# External_Camera_HAT_Regulators.net
KiCad netlist of a schematic drawn in Altium Designer
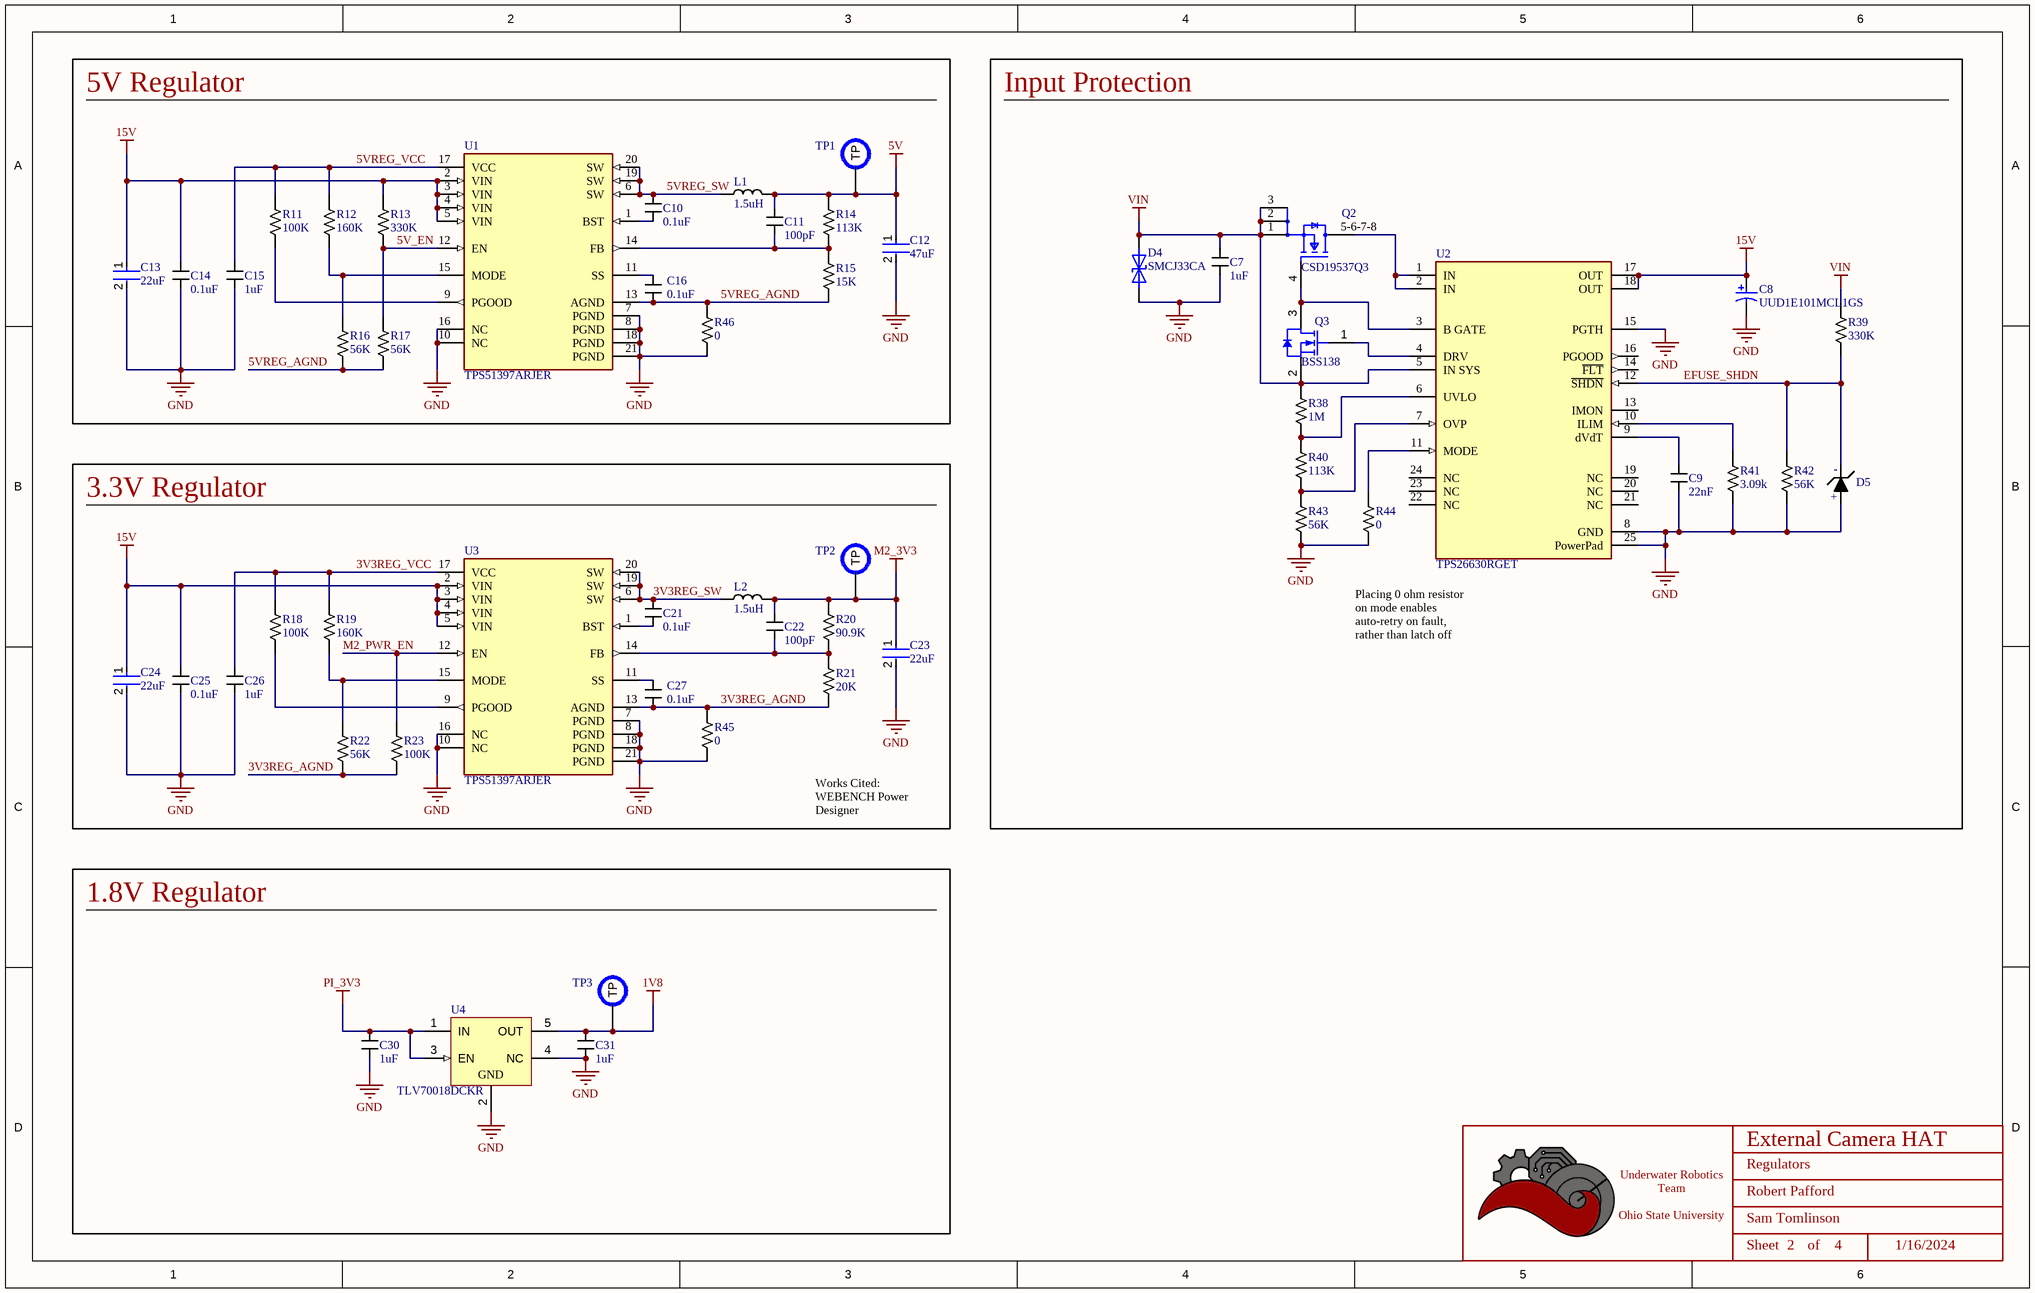
[diagram p0: External_Camera_HAT_Regulators.SchDoc]

(export (version "E")
  (design (tool "Eeschema 10.0.6"))
  (components
    (comp (ref "C7")
      (value "1uF")
      (footprint "CAPACITOR_0603")
      (description "Cap 1uF 25V +/-10%\r\nCeramic 0603")
      (fields
        (field (name "TOLERANCE") "+/- 10%")
        (field (name "VOLTAGE") "16V")
        (field (name "MADE BY") "Flip B")
      )
      (libsource (lib "Capacitors") (part "CAPACITOR_1uF_0603_25V"))
    )
    (comp (ref "C8")
      (value "UUD1E101MCL1GS")
      (footprint "NIC-CAPA2-6.3X7.7_V")
      (fields (field (name "MANUFACTURER") "Nichicon"))
      (libsource (lib "Altium Content Vault") (part "NIC-CAP-P-2"))
    )
    (comp (ref "C9")
      (value "22nF")
      (footprint "CAPACITOR_0402")
      (description "Cap 22nF 25V +/-10%\r\nCeramic 0402")
      (fields
        (field (name "TOLERANCE") "+/- 10%")
        (field (name "VOLTAGE") "25V")
        (field (name "MADE BY") "Robert Pafford")
      )
      (libsource (lib "Capacitors") (part "CAPACITOR_0.022uF_0402"))
    )
    (comp (ref "C10")
      (value "0.1uF")
      (footprint "CAPACITOR_0402")
      (description "Cap 100nF 25V +/-10%\r\nCeramic 0402")
      (fields
        (field (name "TOLERANCE") "+/- 10%")
        (field (name "VOLTAGE") "25V")
        (field (name "MADE BY") "Robert Pafford")
      )
      (libsource (lib "Capacitors") (part "CAPACITOR_0.1uF_0402"))
    )
    (comp (ref "C11")
      (value "100pF")
      (footprint "CAPACITOR_0402")
      (description "Cap 100pF 25V +/-10%\r\nCeramic 0402")
      (fields
        (field (name "TOLERANCE") "+/- 10%")
        (field (name "VOLTAGE") "25V")
        (field (name "MADE BY") "Robert Pafford")
      )
      (libsource (lib "Capacitors") (part "CAPACITOR_0.0001uF_0402"))
    )
    (comp (ref "C12")
      (value "GRM31CR61A476KE15L")
      (footprint "FP-GRM31C-0_2-e0_3_0_8-MFG")
      (description "Chip Multilayer Ceramic Capacitors for General Purpose, 1206, 47uF, X5R, 15%, 10%, 10V")
      (fields
        (field (name "TOLERANCE") "10%")
        (field (name "VOLTAGE") "10V")
        (field (name "CAPACITANCE") "47uF")
      )
      (libsource (lib "Altium Content Vault") (part "02cd4be3c70576c341d710602a673aa"))
    )
    (comp (ref "C13")
      (value "C2012X5R1V226M125AC")
      (footprint "FP-C2012-125-0_2-MFG")
      (description "Multilayer Ceramic Capacitors 22μF ±20% 35V X5R SMD 0805")
      (fields (field (name "TOLERANCE") "20%") (field (name "CAPACITANCE") "22uF"))
      (libsource (lib "Altium Content Vault") (part "b4654b650e69147ec39a6b967a45e02"))
    )
    (comp (ref "C14")
      (value "0.1uF")
      (footprint "CAPACITOR_0402")
      (description "Cap 100nF 25V +/-10%\r\nCeramic 0402")
      (fields
        (field (name "TOLERANCE") "+/- 10%")
        (field (name "VOLTAGE") "25V")
        (field (name "MADE BY") "Robert Pafford")
      )
      (libsource (lib "Capacitors") (part "CAPACITOR_0.1uF_0402"))
    )
    (comp (ref "C15")
      (value "1uF")
      (footprint "CAPACITOR_0402")
      (description "Cap 1uF 16V +/-10%\r\nCeramic 0402")
      (fields
        (field (name "TOLERANCE") "+/- 10%")
        (field (name "VOLTAGE") "16V")
        (field (name "MADE BY") "Robert Pafford")
      )
      (libsource (lib "Capacitors") (part "CAPACITOR_1uF_0402"))
    )
    (comp (ref "C16")
      (value "0.1uF")
      (footprint "CAPACITOR_0402")
      (description "Cap 100nF 25V +/-10%\r\nCeramic 0402")
      (fields
        (field (name "TOLERANCE") "+/- 10%")
        (field (name "VOLTAGE") "25V")
        (field (name "MADE BY") "Robert Pafford")
      )
      (libsource (lib "Capacitors") (part "CAPACITOR_0.1uF_0402"))
    )
    (comp (ref "C21")
      (value "0.1uF")
      (footprint "CAPACITOR_0402")
      (description "Cap 100nF 25V +/-10%\r\nCeramic 0402")
      (fields
        (field (name "TOLERANCE") "+/- 10%")
        (field (name "VOLTAGE") "25V")
        (field (name "MADE BY") "Robert Pafford")
      )
      (libsource (lib "Capacitors") (part "CAPACITOR_0.1uF_0402"))
    )
    (comp (ref "C22")
      (value "100pF")
      (footprint "CAPACITOR_0402")
      (description "Cap 100pF 25V +/-10%\r\nCeramic 0402")
      (fields
        (field (name "TOLERANCE") "+/- 10%")
        (field (name "VOLTAGE") "25V")
        (field (name "MADE BY") "Robert Pafford")
      )
      (libsource (lib "Capacitors") (part "CAPACITOR_0.0001uF_0402"))
    )
    (comp (ref "C23")
      (value "C2012X5R1V226M125AC")
      (footprint "FP-C2012-125-0_2-MFG")
      (description "Multilayer Ceramic Capacitors 22μF ±20% 35V X5R SMD 0805")
      (fields (field (name "TOLERANCE") "20%") (field (name "CAPACITANCE") "22uF"))
      (libsource (lib "Altium Content Vault") (part "b4654b650e69147ec39a6b967a45e02"))
    )
    (comp (ref "C24")
      (value "C2012X5R1V226M125AC")
      (footprint "FP-C2012-125-0_2-MFG")
      (description "Multilayer Ceramic Capacitors 22μF ±20% 35V X5R SMD 0805")
      (fields (field (name "TOLERANCE") "20%") (field (name "CAPACITANCE") "22uF"))
      (libsource (lib "Altium Content Vault") (part "b4654b650e69147ec39a6b967a45e02"))
    )
    (comp (ref "C25")
      (value "0.1uF")
      (footprint "CAPACITOR_0402")
      (description "Cap 100nF 25V +/-10%\r\nCeramic 0402")
      (fields
        (field (name "TOLERANCE") "+/- 10%")
        (field (name "VOLTAGE") "25V")
        (field (name "MADE BY") "Robert Pafford")
      )
      (libsource (lib "Capacitors") (part "CAPACITOR_0.1uF_0402"))
    )
    (comp (ref "C26")
      (value "1uF")
      (footprint "CAPACITOR_0402")
      (description "Cap 1uF 16V +/-10%\r\nCeramic 0402")
      (fields
        (field (name "TOLERANCE") "+/- 10%")
        (field (name "VOLTAGE") "16V")
        (field (name "MADE BY") "Robert Pafford")
      )
      (libsource (lib "Capacitors") (part "CAPACITOR_1uF_0402"))
    )
    (comp (ref "C27")
      (value "0.1uF")
      (footprint "CAPACITOR_0402")
      (description "Cap 100nF 25V +/-10%\r\nCeramic 0402")
      (fields
        (field (name "TOLERANCE") "+/- 10%")
        (field (name "VOLTAGE") "25V")
        (field (name "MADE BY") "Robert Pafford")
      )
      (libsource (lib "Capacitors") (part "CAPACITOR_0.1uF_0402"))
    )
    (comp (ref "C30")
      (value "1uF")
      (footprint "CAPACITOR_0402")
      (description "Cap 1uF 16V +/-10%\r\nCeramic 0402")
      (fields
        (field (name "TOLERANCE") "+/- 10%")
        (field (name "VOLTAGE") "16V")
        (field (name "MADE BY") "Robert Pafford")
      )
      (libsource (lib "Capacitors") (part "CAPACITOR_1uF_0402"))
    )
    (comp (ref "C31")
      (value "1uF")
      (footprint "CAPACITOR_0402")
      (description "Cap 1uF 16V +/-10%\r\nCeramic 0402")
      (fields
        (field (name "TOLERANCE") "+/- 10%")
        (field (name "VOLTAGE") "16V")
        (field (name "MADE BY") "Robert Pafford")
      )
      (libsource (lib "Capacitors") (part "CAPACITOR_1uF_0402"))
    )
    (comp (ref "D4")
      (value "SMCJ33CA")
      (footprint "DIOM7959X262N")
      (description "53.3V Clamp 28.1A Ipp Tvs Diode Surface Mount SMC (DO-214AB)")
      (fields (field (name "MF") "Bourns Inc."))
      (libsource (lib "Diodes") (part "SMCJ33CA"))
    )
    (comp (ref "D5")
      (value "Zener_Diode_3.3V_250mW_1")
      (footprint "SOD-123")
      (description "Zener Diode ¦ 3.3 V ¦ 250 mW ¦ SOT-23")
      (fields (field (name "POWER") "410mW") (field (name "MADE BY") "Nathan A"))
      (libsource (lib "Diodes") (part "Zener_Diode_3.3V_250mW_1"))
    )
    (comp (ref "L1")
      (value "1.5uH")
      (footprint "IHLP2525EZ")
      (description "Inductor Shielded 1.5uH 12A +/-20%")
      (fields
        (field (name "TOLERANCE") "+/- 20%")
        (field (name "Comment") "1.5uH Shielded")
        (field (name "MADE BY") "Robert Pafford")
      )
      (libsource (lib "Inductors") (part "INDUCTOR_1.5uH_IHLP2525EZ_1"))
    )
    (comp (ref "L2")
      (value "1.5uH")
      (footprint "IHLP2525EZ")
      (description "Inductor Shielded 1.5uH 12A +/-20%")
      (fields
        (field (name "TOLERANCE") "+/- 20%")
        (field (name "Comment") "1.5uH Shielded")
        (field (name "MADE BY") "Robert Pafford")
      )
      (libsource (lib "Inductors") (part "INDUCTOR_1.5uH_IHLP2525EZ_1"))
    )
    (comp (ref "Q2")
      (value "CSD19537Q3")
      (footprint "FP-DQG0008A-MFG")
      (description "MOSFET N-CH 100V 50A 8VSON")
      (libsource (lib "Altium Content Vault") (part "7382af88e928fdc71488234cfaaf11c"))
    )
    (comp (ref "Q3")
      (value "BSS138")
      (footprint "FAIR-SOT23-3_V")
      (fields (field (name "MANUFACTURER") "Fairchild") (field (name "POWER") "360mW"))
      (libsource (lib "Ohio State Capstone Team 20") (part "NEMOS-GSD-3"))
    )
    (comp (ref "R11")
      (value "100k Ohm 1% 1/16W")
      (footprint "RESISTOR_0402")
      (description "RES 100k OHM 1% 1/16W 0402")
      (fields
        (field (name "TOLERANCE") "+/- 1%")
        (field (name "VALUE  (OHMS)") "100K")
        (field (name "MADE BY") "Robert Pafford")
      )
      (libsource (lib "Resistors") (part "RESISTOR_100K_0402"))
    )
    (comp (ref "R12")
      (value "160k Ohm 1% 1/16W")
      (footprint "RESISTOR_0402")
      (description "RES 160k OHM 1% 1/16W 0402")
      (fields
        (field (name "TOLERANCE") "+/- 1%")
        (field (name "VALUE  (OHMS)") "160K")
        (field (name "MADE BY") "Robert Pafford")
      )
      (libsource (lib "Resistors") (part "RESISTOR_160K_0402"))
    )
    (comp (ref "R13")
      (value "330k Ohm 1% 1/16W")
      (footprint "RESISTOR_0402")
      (description "RES 330k OHM 1% 1/16W 0402")
      (fields
        (field (name "TOLERANCE") "+/- 1%")
        (field (name "VALUE  (OHMS)") "330K")
        (field (name "MADE BY") "Robert Pafford")
      )
      (libsource (lib "Resistors") (part "RESISTOR_330K_0402"))
    )
    (comp (ref "R14")
      (value "113k Ohm 1% 1/16W")
      (footprint "RESISTOR_0402")
      (description "RES 113k OHM 1% 1/16W 0402")
      (fields
        (field (name "TOLERANCE") "+/- 1%")
        (field (name "VALUE  (OHMS)") "113K")
        (field (name "MADE BY") "Robert Pafford")
      )
      (libsource (lib "Resistors") (part "RESISTOR_113K_0402"))
    )
    (comp (ref "R15")
      (value "15k Ohm 1% 1/16W")
      (footprint "RESISTOR_0402")
      (description "RES 15k OHM 1% 1/16W 0402")
      (fields
        (field (name "TOLERANCE") "+/- 1%")
        (field (name "VALUE  (OHMS)") "15K")
        (field (name "MADE BY") "Robert Pafford")
      )
      (libsource (lib "Resistors") (part "RESISTOR_15K_0402"))
    )
    (comp (ref "R16")
      (value "56k Ohm 1% 1/16W")
      (footprint "RESISTOR_0402")
      (description "RES 56k OHM 1% 1/16W 0402")
      (fields
        (field (name "TOLERANCE") "+/- 1%")
        (field (name "VALUE  (OHMS)") "56K")
        (field (name "MADE BY") "Robert Pafford")
      )
      (libsource (lib "Resistors") (part "RESISTOR_56K_0402"))
    )
    (comp (ref "R17")
      (value "56k Ohm 1% 1/16W")
      (footprint "RESISTOR_0402")
      (description "RES 56k OHM 1% 1/16W 0402")
      (fields
        (field (name "TOLERANCE") "+/- 1%")
        (field (name "VALUE  (OHMS)") "56K")
        (field (name "MADE BY") "Robert Pafford")
      )
      (libsource (lib "Resistors") (part "RESISTOR_56K_0402"))
    )
    (comp (ref "R18")
      (value "100k Ohm 1% 1/16W")
      (footprint "RESISTOR_0402")
      (description "RES 100k OHM 1% 1/16W 0402")
      (fields
        (field (name "TOLERANCE") "+/- 1%")
        (field (name "VALUE  (OHMS)") "100K")
        (field (name "MADE BY") "Robert Pafford")
      )
      (libsource (lib "Resistors") (part "RESISTOR_100K_0402"))
    )
    (comp (ref "R19")
      (value "160k Ohm 1% 1/16W")
      (footprint "RESISTOR_0402")
      (description "RES 160k OHM 1% 1/16W 0402")
      (fields
        (field (name "TOLERANCE") "+/- 1%")
        (field (name "VALUE  (OHMS)") "160K")
        (field (name "MADE BY") "Robert Pafford")
      )
      (libsource (lib "Resistors") (part "RESISTOR_160K_0402"))
    )
    (comp (ref "R20")
      (value "90.9k Ohm 1% 1/16W")
      (footprint "RESISTOR_0402")
      (description "RES 90.9k OHM 1% 1/16W 0402")
      (fields
        (field (name "TOLERANCE") "+/- 1%")
        (field (name "VALUE  (OHMS)") "90.9K")
        (field (name "MADE BY") "Robert Pafford")
      )
      (libsource (lib "Resistors") (part "RESISTOR_90.9K_0402"))
    )
    (comp (ref "R21")
      (value "20k Ohm 1% 1/16W")
      (footprint "RESISTOR_0402")
      (description "RES 20k OHM 1% 1/16W 0402")
      (fields
        (field (name "TOLERANCE") "+/- 1%")
        (field (name "VALUE  (OHMS)") "20K")
        (field (name "MADE BY") "Robert Pafford")
      )
      (libsource (lib "Resistors") (part "RESISTOR_20K_0402"))
    )
    (comp (ref "R22")
      (value "56k Ohm 1% 1/16W")
      (footprint "RESISTOR_0402")
      (description "RES 56k OHM 1% 1/16W 0402")
      (fields
        (field (name "TOLERANCE") "+/- 1%")
        (field (name "VALUE  (OHMS)") "56K")
        (field (name "MADE BY") "Robert Pafford")
      )
      (libsource (lib "Resistors") (part "RESISTOR_56K_0402"))
    )
    (comp (ref "R23")
      (value "100k Ohm 1% 1/16W")
      (footprint "RESISTOR_0402")
      (description "RES 100k OHM 1% 1/16W 0402")
      (fields
        (field (name "TOLERANCE") "+/- 1%")
        (field (name "VALUE  (OHMS)") "100K")
        (field (name "MADE BY") "Robert Pafford")
      )
      (libsource (lib "Resistors") (part "RESISTOR_100K_0402"))
    )
    (comp (ref "R38")
      (value "1M Ohm 1% 1/16W")
      (footprint "RESISTOR_0402")
      (description "RES 1M OHM 1% 1/16W 0402")
      (fields
        (field (name "TOLERANCE") "+/- 1%")
        (field (name "VALUE  (OHMS)") "1M")
        (field (name "MADE BY") "Robert Pafford")
      )
      (libsource (lib "Resistors") (part "RESISTOR_1M_0402"))
    )
    (comp (ref "R39")
      (value "330k Ohm 1% 1/16W")
      (footprint "RESISTOR_0402")
      (description "RES 330k OHM 1% 1/16W 0402")
      (fields
        (field (name "TOLERANCE") "+/- 1%")
        (field (name "VALUE  (OHMS)") "330K")
        (field (name "MADE BY") "Robert Pafford")
      )
      (libsource (lib "Resistors") (part "RESISTOR_330K_0402"))
    )
    (comp (ref "R40")
      (value "113k Ohm 1% 1/16W")
      (footprint "RESISTOR_0402")
      (description "RES 113k OHM 1% 1/16W 0402")
      (fields
        (field (name "TOLERANCE") "+/- 1%")
        (field (name "VALUE  (OHMS)") "113K")
        (field (name "MADE BY") "Robert Pafford")
      )
      (libsource (lib "Resistors") (part "RESISTOR_113K_0402"))
    )
    (comp (ref "R41")
      (value "3.09k Ohm 1% 1/16W")
      (footprint "RESISTOR_0402")
      (description "RES 3.09k OHM 1% 1/16W 0402")
      (fields
        (field (name "TOLERANCE") "+/- 1%")
        (field (name "VALUE  (OHMS)") "3.09k")
        (field (name "MADE BY") "Robert Pafford")
      )
      (libsource (lib "Resistors") (part "RESISTOR_3.09K_0402"))
    )
    (comp (ref "R42")
      (value "56k Ohm 1% 1/16W")
      (footprint "RESISTOR_0402")
      (description "RES 56k OHM 1% 1/16W 0402")
      (fields
        (field (name "TOLERANCE") "+/- 1%")
        (field (name "VALUE  (OHMS)") "56K")
        (field (name "MADE BY") "Robert Pafford")
      )
      (libsource (lib "Resistors") (part "RESISTOR_56K_0402"))
    )
    (comp (ref "R43")
      (value "56k Ohm 1% 1/16W")
      (footprint "RESISTOR_0402")
      (description "RES 56k OHM 1% 1/16W 0402")
      (fields
        (field (name "TOLERANCE") "+/- 1%")
        (field (name "VALUE  (OHMS)") "56K")
        (field (name "MADE BY") "Robert Pafford")
      )
      (libsource (lib "Resistors") (part "RESISTOR_56K_0402"))
    )
    (comp (ref "R44")
      (value "0 Ohm 1% 1/16W")
      (footprint "RESISTOR_0402")
      (description "RES 0 OHM 1% 1/16W 0402")
      (fields
        (field (name "TOLERANCE") "+/- 1%")
        (field (name "VALUE  (OHMS)") "0")
        (field (name "MADE BY") "Robert Pafford")
      )
      (libsource (lib "Resistors") (part "RESISTOR_0_0402"))
    )
    (comp (ref "R45")
      (value "0 Ohm 1% 1/16W")
      (footprint "RESISTOR_0402")
      (description "RES 0 OHM 1% 1/16W 0402")
      (fields
        (field (name "TOLERANCE") "+/- 1%")
        (field (name "VALUE  (OHMS)") "0")
        (field (name "MADE BY") "Robert Pafford")
      )
      (libsource (lib "Resistors") (part "RESISTOR_0_0402"))
    )
    (comp (ref "R46")
      (value "0 Ohm 1% 1/16W")
      (footprint "RESISTOR_0402")
      (description "RES 0 OHM 1% 1/16W 0402")
      (fields
        (field (name "TOLERANCE") "+/- 1%")
        (field (name "VALUE  (OHMS)") "0")
        (field (name "MADE BY") "Robert Pafford")
      )
      (libsource (lib "Resistors") (part "RESISTOR_0_0402"))
    )
    (comp (ref "TP1")
      (value "PCB Test Point")
      (footprint "TESTPOINT_1.2MM")
      (fields (field (name "MADE BY") "Robert Pafford"))
      (libsource (lib "Connectors") (part "TESTPOINT"))
    )
    (comp (ref "TP2")
      (value "PCB Test Point")
      (footprint "TESTPOINT_1.2MM")
      (fields (field (name "MADE BY") "Robert Pafford"))
      (libsource (lib "Connectors") (part "TESTPOINT"))
    )
    (comp (ref "TP3")
      (value "PCB Test Point")
      (footprint "TESTPOINT_1.2MM")
      (fields (field (name "MADE BY") "Robert Pafford"))
      (libsource (lib "Connectors") (part "TESTPOINT"))
    )
    (comp (ref "U1")
      (value "TPS51397ARJER")
      (footprint "FP-RJE0020B-MFG")
      (description "10-A SYNCHRONOUS STEP-DOWN REGUL")
      (libsource (lib "Altium Content Vault") (part "ab47a50a5143bf718f7c4e945efebe0"))
    )
    (comp (ref "U2")
      (value "TPS26630RGET")
      (footprint "FP-RGE0024H-MFG")
      (description "POWER MANAGEMENT")
      (libsource (lib "Altium Content Vault") (part "92e6325a0b2cd7354d0d77963e83935"))
    )
    (comp (ref "U3")
      (value "TPS51397ARJER")
      (footprint "FP-RJE0020B-MFG")
      (description "10-A SYNCHRONOUS STEP-DOWN REGUL")
      (libsource (lib "Altium Content Vault") (part "ab47a50a5143bf718f7c4e945efebe0"))
    )
    (comp (ref "U4")
      (value "TLV70018DCKR")
      (footprint "DCK0005A_N")
      (fields (field (name "MANUFACTURER") "Texas Instruments"))
      (libsource (lib "Altium Content Vault") (part "TI-TXX7XXXX-5"))
    )
  )
  (nets
    (net (code "1") (name "/3V3REG_AGND") (class "Default")
      (node (ref "C27") (pin "2") (pinfunction "2_2") (pintype "passive"))
      (node (ref "R21") (pin "2") (pinfunction "2_2") (pintype "passive"))
      (node (ref "R22") (pin "2") (pinfunction "2_2") (pintype "passive"))
      (node (ref "R23") (pin "2") (pinfunction "2_2") (pintype "passive"))
      (node (ref "R45") (pin "1") (pinfunction "1_1") (pintype "passive"))
      (node (ref "U3") (pin "13") (pinfunction "AGND_13") (pintype "power_in"))
    )
    (net (code "2") (name "/3V3REG_SW") (class "Default")
      (node (ref "C21") (pin "1") (pinfunction "1_1") (pintype "passive"))
      (node (ref "L2") (pin "2") (pinfunction "2_2") (pintype "passive"))
      (node (ref "U3") (pin "19") (pinfunction "SW_19") (pintype "input"))
      (node (ref "U3") (pin "20") (pinfunction "SW_20") (pintype "input"))
      (node (ref "U3") (pin "6") (pinfunction "SW_6") (pintype "input"))
    )
    (net (code "3") (name "/3V3REG_VCC") (class "Default")
      (node (ref "C26") (pin "1") (pinfunction "1_1") (pintype "passive"))
      (node (ref "R18") (pin "1") (pinfunction "1_1") (pintype "passive"))
      (node (ref "R19") (pin "1") (pinfunction "1_1") (pintype "passive"))
      (node (ref "U3") (pin "17") (pinfunction "VCC_17") (pintype "power_in"))
    )
    (net (code "4") (name "/5VREG_AGND") (class "Default")
      (node (ref "C16") (pin "2") (pinfunction "2_2") (pintype "passive"))
      (node (ref "R15") (pin "2") (pinfunction "2_2") (pintype "passive"))
      (node (ref "R16") (pin "2") (pinfunction "2_2") (pintype "passive"))
      (node (ref "R17") (pin "2") (pinfunction "2_2") (pintype "passive"))
      (node (ref "R46") (pin "1") (pinfunction "1_1") (pintype "passive"))
      (node (ref "U1") (pin "13") (pinfunction "AGND_13") (pintype "power_in"))
    )
    (net (code "5") (name "/5VREG_SW") (class "Default")
      (node (ref "C10") (pin "1") (pinfunction "1_1") (pintype "passive"))
      (node (ref "L1") (pin "2") (pinfunction "2_2") (pintype "passive"))
      (node (ref "U1") (pin "19") (pinfunction "SW_19") (pintype "input"))
      (node (ref "U1") (pin "20") (pinfunction "SW_20") (pintype "input"))
      (node (ref "U1") (pin "6") (pinfunction "SW_6") (pintype "input"))
    )
    (net (code "6") (name "/5VREG_VCC") (class "Default")
      (node (ref "C15") (pin "1") (pinfunction "1_1") (pintype "passive"))
      (node (ref "R11") (pin "1") (pinfunction "1_1") (pintype "passive"))
      (node (ref "R12") (pin "1") (pinfunction "1_1") (pintype "passive"))
      (node (ref "U1") (pin "17") (pinfunction "VCC_17") (pintype "power_in"))
    )
    (net (code "7") (name "/5V_EN") (class "Default")
      (node (ref "R13") (pin "2") (pinfunction "2_2") (pintype "passive"))
      (node (ref "R17") (pin "1") (pinfunction "1_1") (pintype "passive"))
      (node (ref "U1") (pin "12") (pinfunction "EN_12") (pintype "input"))
    )
    (net (code "8") (name "/EFUSE_SHDN") (class "Default")
      (node (ref "D5") (pin "2") (pinfunction "2_2") (pintype "passive"))
      (node (ref "R39") (pin "2") (pinfunction "2_2") (pintype "passive"))
      (node (ref "R42") (pin "1") (pinfunction "1_1") (pintype "passive"))
      (node (ref "U2") (pin "12") (pinfunction "~{SHDN}_12") (pintype "input"))
    )
    (net (code "9") (name "/M2_PWR_EN") (class "Default")
      (node (ref "R23") (pin "1") (pinfunction "1_1") (pintype "passive"))
      (node (ref "U3") (pin "12") (pinfunction "EN_12") (pintype "input"))
    )
    (net (code "10") (name "1V8") (class "Default")
      (node (ref "C31") (pin "1") (pinfunction "1_1") (pintype "passive"))
      (node (ref "TP3") (pin "TP") (pinfunction "TP_TP") (pintype "passive"))
      (node (ref "U4") (pin "5") (pinfunction "OUT_5") (pintype "power_in"))
    )
    (net (code "11") (name "5V") (class "Default")
      (node (ref "C11") (pin "1") (pinfunction "1_1") (pintype "passive"))
      (node (ref "C12") (pin "1") (pinfunction "1_1") (pintype "passive"))
      (node (ref "L1") (pin "1") (pinfunction "1_1") (pintype "passive"))
      (node (ref "R14") (pin "1") (pinfunction "1_1") (pintype "passive"))
      (node (ref "TP1") (pin "TP") (pinfunction "TP_TP") (pintype "passive"))
    )
    (net (code "12") (name "15V") (class "Default")
      (node (ref "C13") (pin "1") (pinfunction "1_1") (pintype "passive"))
      (node (ref "C14") (pin "1") (pinfunction "1_1") (pintype "passive"))
      (node (ref "C24") (pin "1") (pinfunction "1_1") (pintype "passive"))
      (node (ref "C25") (pin "1") (pinfunction "1_1") (pintype "passive"))
      (node (ref "C8") (pin "1") (pinfunction "1_1") (pintype "passive"))
      (node (ref "R13") (pin "1") (pinfunction "1_1") (pintype "passive"))
      (node (ref "U1") (pin "2") (pinfunction "VIN_2") (pintype "input"))
      (node (ref "U1") (pin "3") (pinfunction "VIN_3") (pintype "input"))
      (node (ref "U1") (pin "4") (pinfunction "VIN_4") (pintype "input"))
      (node (ref "U1") (pin "5") (pinfunction "VIN_5") (pintype "input"))
      (node (ref "U2") (pin "17") (pinfunction "OUT_17") (pintype "power_in"))
      (node (ref "U2") (pin "18") (pinfunction "OUT_18") (pintype "power_in"))
      (node (ref "U3") (pin "2") (pinfunction "VIN_2") (pintype "input"))
      (node (ref "U3") (pin "3") (pinfunction "VIN_3") (pintype "input"))
      (node (ref "U3") (pin "4") (pinfunction "VIN_4") (pintype "input"))
      (node (ref "U3") (pin "5") (pinfunction "VIN_5") (pintype "input"))
    )
    (net (code "13") (name "GND") (class "Default")
      (node (ref "C12") (pin "2") (pinfunction "2_2") (pintype "passive"))
      (node (ref "C13") (pin "2") (pinfunction "2_2") (pintype "passive"))
      (node (ref "C14") (pin "2") (pinfunction "2_2") (pintype "passive"))
      (node (ref "C15") (pin "2") (pinfunction "2_2") (pintype "passive"))
      (node (ref "C23") (pin "2") (pinfunction "2_2") (pintype "passive"))
      (node (ref "C24") (pin "2") (pinfunction "2_2") (pintype "passive"))
      (node (ref "C25") (pin "2") (pinfunction "2_2") (pintype "passive"))
      (node (ref "C26") (pin "2") (pinfunction "2_2") (pintype "passive"))
      (node (ref "C30") (pin "2") (pinfunction "2_2") (pintype "passive"))
      (node (ref "C31") (pin "2") (pinfunction "2_2") (pintype "passive"))
      (node (ref "C7") (pin "2") (pinfunction "2_2") (pintype "passive"))
      (node (ref "C8") (pin "2") (pinfunction "2_2") (pintype "passive"))
      (node (ref "C9") (pin "2") (pinfunction "2_2") (pintype "passive"))
      (node (ref "D4") (pin "1") (pinfunction "1_1") (pintype "passive"))
      (node (ref "D5") (pin "1") (pinfunction "1_1") (pintype "passive"))
      (node (ref "R41") (pin "2") (pinfunction "2_2") (pintype "passive"))
      (node (ref "R42") (pin "2") (pinfunction "2_2") (pintype "passive"))
      (node (ref "R43") (pin "2") (pinfunction "2_2") (pintype "passive"))
      (node (ref "R44") (pin "2") (pinfunction "2_2") (pintype "passive"))
      (node (ref "R45") (pin "2") (pinfunction "2_2") (pintype "passive"))
      (node (ref "R46") (pin "2") (pinfunction "2_2") (pintype "passive"))
      (node (ref "U1") (pin "10") (pinfunction "NC_10") (pintype "passive"))
      (node (ref "U1") (pin "16") (pinfunction "NC_16") (pintype "passive"))
      (node (ref "U1") (pin "18") (pinfunction "PGND_18") (pintype "power_in"))
      (node (ref "U1") (pin "21") (pinfunction "PGND_21") (pintype "power_in"))
      (node (ref "U1") (pin "7") (pinfunction "PGND_7") (pintype "power_in"))
      (node (ref "U1") (pin "8") (pinfunction "PGND_8") (pintype "power_in"))
      (node (ref "U2") (pin "15") (pinfunction "PGTH_15") (pintype "passive"))
      (node (ref "U2") (pin "25") (pinfunction "PowerPad_25") (pintype "power_in"))
      (node (ref "U2") (pin "8") (pinfunction "GND_8") (pintype "power_in"))
      (node (ref "U3") (pin "10") (pinfunction "NC_10") (pintype "passive"))
      (node (ref "U3") (pin "16") (pinfunction "NC_16") (pintype "passive"))
      (node (ref "U3") (pin "18") (pinfunction "PGND_18") (pintype "power_in"))
      (node (ref "U3") (pin "21") (pinfunction "PGND_21") (pintype "power_in"))
      (node (ref "U3") (pin "7") (pinfunction "PGND_7") (pintype "power_in"))
      (node (ref "U3") (pin "8") (pinfunction "PGND_8") (pintype "power_in"))
      (node (ref "U4") (pin "2") (pinfunction "GND_2") (pintype "power_in"))
      (node (ref "U4") (pin "4") (pinfunction "NC_4") (pintype "passive"))
    )
    (net (code "14") (name "M2_3V3") (class "Default")
      (node (ref "C22") (pin "1") (pinfunction "1_1") (pintype "passive"))
      (node (ref "C23") (pin "1") (pinfunction "1_1") (pintype "passive"))
      (node (ref "L2") (pin "1") (pinfunction "1_1") (pintype "passive"))
      (node (ref "R20") (pin "1") (pinfunction "1_1") (pintype "passive"))
      (node (ref "TP2") (pin "TP") (pinfunction "TP_TP") (pintype "passive"))
    )
    (net (code "15") (name "Net-(Q2-D)") (class "Default")
      (node (ref "Q2") (pin "5-6-7-8") (pinfunction "D_5-6-7-8") (pintype "passive"))
      (node (ref "U2") (pin "1") (pinfunction "IN_1") (pintype "power_in"))
      (node (ref "U2") (pin "2") (pinfunction "IN_2") (pintype "power_in"))
    )
    (net (code "16") (name "Net-(Q2-G)") (class "Default")
      (node (ref "Q2") (pin "4") (pinfunction "G_4") (pintype "passive"))
      (node (ref "Q3") (pin "3") (pinfunction "D_3") (pintype "passive"))
      (node (ref "U2") (pin "3") (pinfunction "B_GATE_3") (pintype "passive"))
    )
    (net (code "17") (name "Net-(Q3-G)") (class "Default")
      (node (ref "Q3") (pin "1") (pinfunction "G_1") (pintype "passive"))
      (node (ref "U2") (pin "4") (pinfunction "DRV_4") (pintype "passive"))
    )
    (net (code "18") (name "Net-(U1-BST)") (class "Default")
      (node (ref "C10") (pin "2") (pinfunction "2_2") (pintype "passive"))
      (node (ref "U1") (pin "1") (pinfunction "BST_1") (pintype "input"))
    )
    (net (code "19") (name "Net-(U1-FB)") (class "Default")
      (node (ref "C11") (pin "2") (pinfunction "2_2") (pintype "passive"))
      (node (ref "R14") (pin "2") (pinfunction "2_2") (pintype "passive"))
      (node (ref "R15") (pin "1") (pinfunction "1_1") (pintype "passive"))
      (node (ref "U1") (pin "14") (pinfunction "FB_14") (pintype "output"))
    )
    (net (code "20") (name "Net-(U1-MODE)") (class "Default")
      (node (ref "R12") (pin "2") (pinfunction "2_2") (pintype "passive"))
      (node (ref "R16") (pin "1") (pinfunction "1_1") (pintype "passive"))
      (node (ref "U1") (pin "15") (pinfunction "MODE_15") (pintype "passive"))
    )
    (net (code "21") (name "Net-(U1-PGOOD)") (class "Default")
      (node (ref "R11") (pin "2") (pinfunction "2_2") (pintype "passive"))
      (node (ref "U1") (pin "9") (pinfunction "PGOOD_9") (pintype "output"))
    )
    (net (code "22") (name "Net-(U1-SS)") (class "Default")
      (node (ref "C16") (pin "1") (pinfunction "1_1") (pintype "passive"))
      (node (ref "U1") (pin "11") (pinfunction "SS_11") (pintype "passive"))
    )
    (net (code "23") (name "Net-(U2-ILIM)") (class "Default")
      (node (ref "R41") (pin "1") (pinfunction "1_1") (pintype "passive"))
      (node (ref "U2") (pin "10") (pinfunction "ILIM_10") (pintype "input"))
    )
    (net (code "24") (name "Net-(U2-MODE)") (class "Default")
      (node (ref "R44") (pin "1") (pinfunction "1_1") (pintype "passive"))
      (node (ref "U2") (pin "11") (pinfunction "MODE_11") (pintype "input"))
    )
    (net (code "25") (name "Net-(U2-OVP)") (class "Default")
      (node (ref "R40") (pin "2") (pinfunction "2_2") (pintype "passive"))
      (node (ref "R43") (pin "1") (pinfunction "1_1") (pintype "passive"))
      (node (ref "U2") (pin "7") (pinfunction "OVP_7") (pintype "input"))
    )
    (net (code "26") (name "Net-(U2-UVLO)") (class "Default")
      (node (ref "R38") (pin "2") (pinfunction "2_2") (pintype "passive"))
      (node (ref "R40") (pin "1") (pinfunction "1_1") (pintype "passive"))
      (node (ref "U2") (pin "6") (pinfunction "UVLO_6") (pintype "passive"))
    )
    (net (code "27") (name "Net-(U2-dVdT)") (class "Default")
      (node (ref "C9") (pin "1") (pinfunction "1_1") (pintype "passive"))
      (node (ref "U2") (pin "9") (pinfunction "dVdT_9") (pintype "passive"))
    )
    (net (code "28") (name "Net-(U3-BST)") (class "Default")
      (node (ref "C21") (pin "2") (pinfunction "2_2") (pintype "passive"))
      (node (ref "U3") (pin "1") (pinfunction "BST_1") (pintype "input"))
    )
    (net (code "29") (name "Net-(U3-FB)") (class "Default")
      (node (ref "C22") (pin "2") (pinfunction "2_2") (pintype "passive"))
      (node (ref "R20") (pin "2") (pinfunction "2_2") (pintype "passive"))
      (node (ref "R21") (pin "1") (pinfunction "1_1") (pintype "passive"))
      (node (ref "U3") (pin "14") (pinfunction "FB_14") (pintype "output"))
    )
    (net (code "30") (name "Net-(U3-MODE)") (class "Default")
      (node (ref "R19") (pin "2") (pinfunction "2_2") (pintype "passive"))
      (node (ref "R22") (pin "1") (pinfunction "1_1") (pintype "passive"))
      (node (ref "U3") (pin "15") (pinfunction "MODE_15") (pintype "passive"))
    )
    (net (code "31") (name "Net-(U3-PGOOD)") (class "Default")
      (node (ref "R18") (pin "2") (pinfunction "2_2") (pintype "passive"))
      (node (ref "U3") (pin "9") (pinfunction "PGOOD_9") (pintype "output"))
    )
    (net (code "32") (name "Net-(U3-SS)") (class "Default")
      (node (ref "C27") (pin "1") (pinfunction "1_1") (pintype "passive"))
      (node (ref "U3") (pin "11") (pinfunction "SS_11") (pintype "passive"))
    )
    (net (code "33") (name "PI_3V3") (class "Default")
      (node (ref "C30") (pin "1") (pinfunction "1_1") (pintype "passive"))
      (node (ref "U4") (pin "1") (pinfunction "IN_1") (pintype "power_in"))
      (node (ref "U4") (pin "3") (pinfunction "EN_3") (pintype "input"))
    )
    (net (code "34") (name "VIN") (class "Default")
      (node (ref "C7") (pin "1") (pinfunction "1_1") (pintype "passive"))
      (node (ref "D4") (pin "2") (pinfunction "2_2") (pintype "passive"))
      (node (ref "Q2") (pin "1") (pinfunction "S_1") (pintype "passive"))
      (node (ref "Q2") (pin "2") (pinfunction "S_2") (pintype "passive"))
      (node (ref "Q2") (pin "3") (pinfunction "S_3") (pintype "passive"))
      (node (ref "Q3") (pin "2") (pinfunction "S_2") (pintype "passive"))
      (node (ref "R38") (pin "1") (pinfunction "1_1") (pintype "passive"))
      (node (ref "R39") (pin "1") (pinfunction "1_1") (pintype "passive"))
      (node (ref "U2") (pin "5") (pinfunction "IN_SYS_5") (pintype "power_in"))
    )
    (net (code "35") (name "unconnected-(U2-IMON-Pad13)") (class "Default")
      (node (ref "U2") (pin "13") (pinfunction "IMON_13") (pintype "passive"))
    )
    (net (code "36") (name "unconnected-(U2-NC-Pad19)") (class "Default")
      (node (ref "U2") (pin "19") (pinfunction "NC_19") (pintype "passive"))
    )
    (net (code "37") (name "unconnected-(U2-NC-Pad20)") (class "Default")
      (node (ref "U2") (pin "20") (pinfunction "NC_20") (pintype "passive"))
    )
    (net (code "38") (name "unconnected-(U2-NC-Pad21)") (class "Default")
      (node (ref "U2") (pin "21") (pinfunction "NC_21") (pintype "passive"))
    )
    (net (code "39") (name "unconnected-(U2-NC-Pad22)") (class "Default")
      (node (ref "U2") (pin "22") (pinfunction "NC_22") (pintype "passive"))
    )
    (net (code "40") (name "unconnected-(U2-NC-Pad23)") (class "Default")
      (node (ref "U2") (pin "23") (pinfunction "NC_23") (pintype "passive"))
    )
    (net (code "41") (name "unconnected-(U2-NC-Pad24)") (class "Default")
      (node (ref "U2") (pin "24") (pinfunction "NC_24") (pintype "passive"))
    )
    (net (code "42") (name "unconnected-(U2-PGOOD-Pad16)") (class "Default")
      (node (ref "U2") (pin "16") (pinfunction "PGOOD_16") (pintype "output"))
    )
    (net (code "43") (name "unconnected-(U2-~{FLT}-Pad14)") (class "Default")
      (node (ref "U2") (pin "14") (pinfunction "~{FLT}_14") (pintype "output"))
    )
  )
)
